# CompletePCB.net
KiCad netlist of a schematic drawn in EAGLE
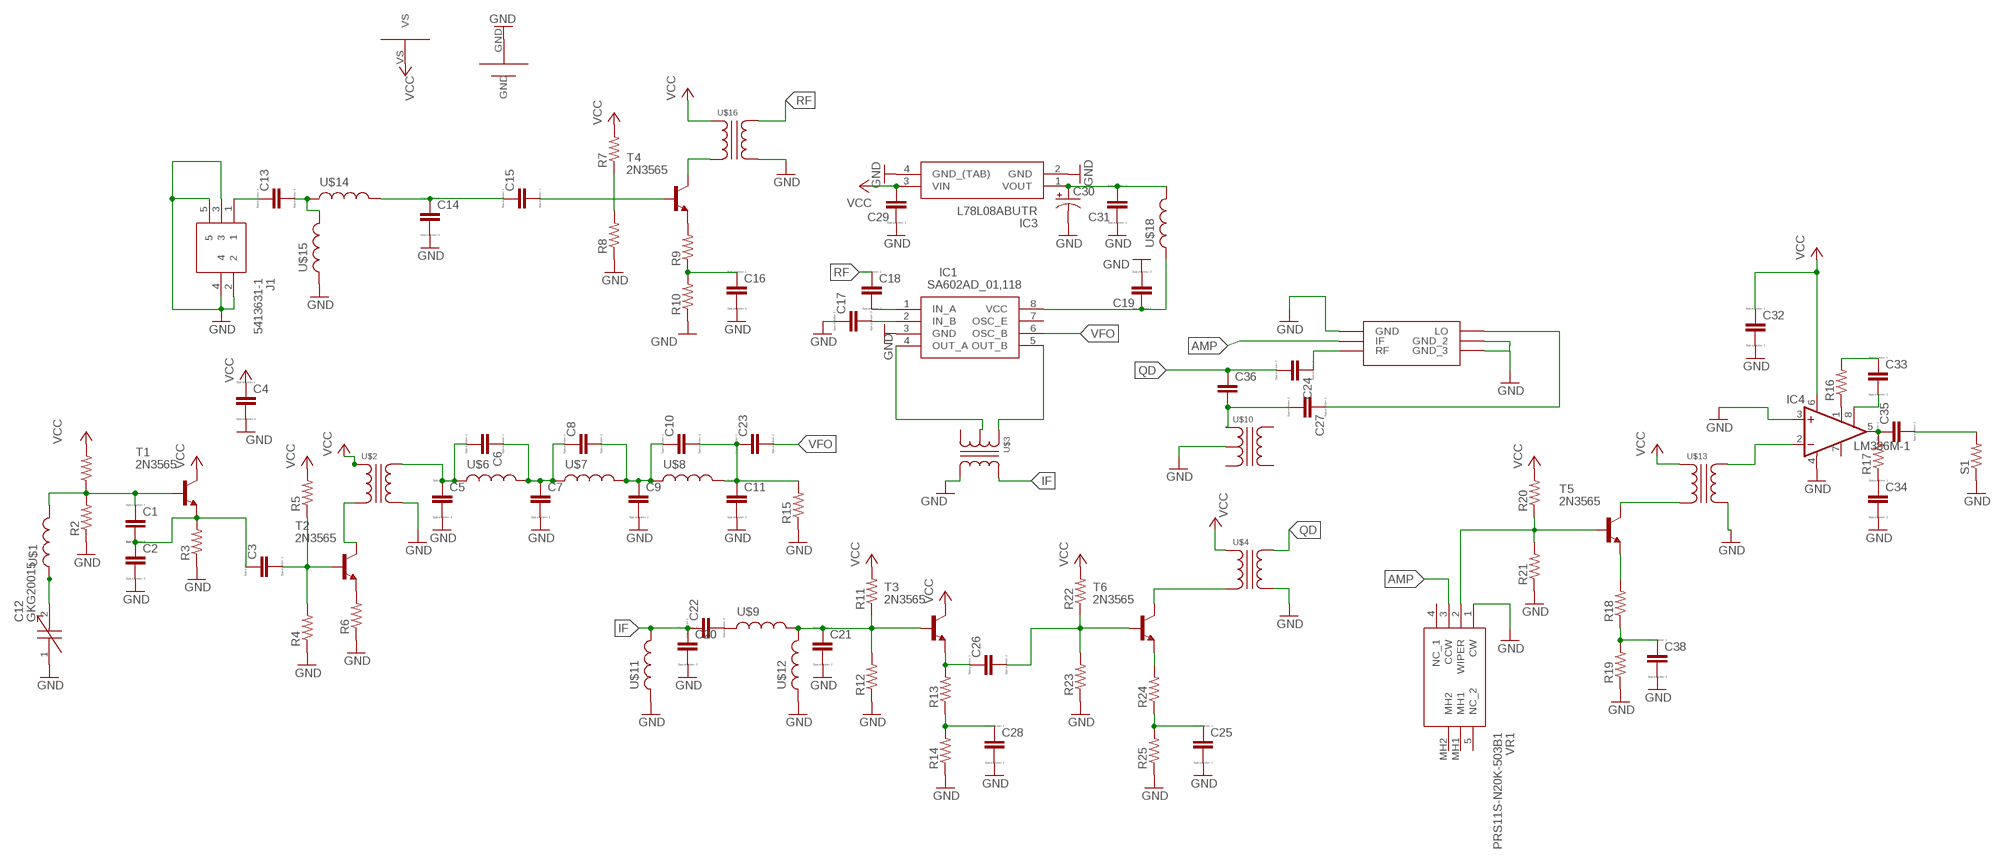
[diagram p0: schematic, sheet 1]

(export (version "E")
  (design (tool "Eeschema 10.0.6"))
  (components
    (comp (ref "C1") (value "C") (footprint "eagle-import:C0805") (libsource (lib "eagle-import") (part "C")))
    (comp (ref "C2") (value "C") (footprint "eagle-import:C0805") (libsource (lib "eagle-import") (part "C")))
    (comp (ref "C3") (value "C") (footprint "eagle-import:C0805") (libsource (lib "eagle-import") (part "C")))
    (comp (ref "C4") (value "C") (footprint "eagle-import:C0805") (libsource (lib "eagle-import") (part "C")))
    (comp (ref "C5") (value "C") (footprint "eagle-import:C0805") (libsource (lib "eagle-import") (part "C")))
    (comp (ref "C6") (value "C") (footprint "eagle-import:C0805") (libsource (lib "eagle-import") (part "C")))
    (comp (ref "C7") (value "C") (footprint "eagle-import:C0805") (libsource (lib "eagle-import") (part "C")))
    (comp (ref "C8") (value "C") (footprint "eagle-import:C0805") (libsource (lib "eagle-import") (part "C")))
    (comp (ref "C9") (value "C") (footprint "eagle-import:C0805") (libsource (lib "eagle-import") (part "C")))
    (comp (ref "C10")
      (value "C")
      (footprint "eagle-import:C0805")
      (libsource (lib "eagle-import") (part "C"))
    )
    (comp (ref "C11")
      (value "C")
      (footprint "eagle-import:C0805")
      (libsource (lib "eagle-import") (part "C"))
    )
    (comp (ref "C12")
      (value "GKG20015")
      (footprint "eagle-import:GKG20015")
      (fields (field (name "MOUSER_PART_NUMBER") "659-GKG20015"))
      (libsource (lib "eagle-import") (part "GKG20015"))
    )
    (comp (ref "C13")
      (value "C")
      (footprint "eagle-import:C0805")
      (libsource (lib "eagle-import") (part "C"))
    )
    (comp (ref "C14")
      (value "C")
      (footprint "eagle-import:C0805")
      (libsource (lib "eagle-import") (part "C"))
    )
    (comp (ref "C15")
      (value "C")
      (footprint "eagle-import:C0805")
      (libsource (lib "eagle-import") (part "C"))
    )
    (comp (ref "C16")
      (value "C")
      (footprint "eagle-import:C0805")
      (libsource (lib "eagle-import") (part "C"))
    )
    (comp (ref "C17")
      (value "C")
      (footprint "eagle-import:C0805")
      (libsource (lib "eagle-import") (part "C"))
    )
    (comp (ref "C18")
      (value "C")
      (footprint "eagle-import:C0805")
      (libsource (lib "eagle-import") (part "C"))
    )
    (comp (ref "C19")
      (value "C")
      (footprint "eagle-import:C0805")
      (libsource (lib "eagle-import") (part "C"))
    )
    (comp (ref "C20")
      (value "C")
      (footprint "eagle-import:C0805")
      (libsource (lib "eagle-import") (part "C"))
    )
    (comp (ref "C21")
      (value "C")
      (footprint "eagle-import:C0805")
      (libsource (lib "eagle-import") (part "C"))
    )
    (comp (ref "C22")
      (value "C")
      (footprint "eagle-import:C0805")
      (libsource (lib "eagle-import") (part "C"))
    )
    (comp (ref "C23")
      (value "C")
      (footprint "eagle-import:C0805")
      (libsource (lib "eagle-import") (part "C"))
    )
    (comp (ref "C24")
      (value "C")
      (footprint "eagle-import:C0805")
      (libsource (lib "eagle-import") (part "C"))
    )
    (comp (ref "C25")
      (value "C")
      (footprint "eagle-import:C0805")
      (libsource (lib "eagle-import") (part "C"))
    )
    (comp (ref "C26")
      (value "C")
      (footprint "eagle-import:C0805")
      (libsource (lib "eagle-import") (part "C"))
    )
    (comp (ref "C27")
      (value "C")
      (footprint "eagle-import:C0805")
      (libsource (lib "eagle-import") (part "C"))
    )
    (comp (ref "C28")
      (value "C")
      (footprint "eagle-import:C0805")
      (libsource (lib "eagle-import") (part "C"))
    )
    (comp (ref "C29")
      (value "C")
      (footprint "eagle-import:C0805")
      (libsource (lib "eagle-import") (part "C"))
    )
    (comp (ref "C30")
      (value "CPOL-US175TMP-0808")
      (footprint "eagle-import:175TMP-0808")
      (libsource (lib "eagle-import") (part "CPOL-US175TMP-0808"))
    )
    (comp (ref "C31")
      (value "C")
      (footprint "eagle-import:C0805")
      (libsource (lib "eagle-import") (part "C"))
    )
    (comp (ref "C32")
      (value "C")
      (footprint "eagle-import:C0805")
      (libsource (lib "eagle-import") (part "C"))
    )
    (comp (ref "C33")
      (value "C")
      (footprint "eagle-import:C0805")
      (libsource (lib "eagle-import") (part "C"))
    )
    (comp (ref "C34")
      (value "C")
      (footprint "eagle-import:C0805")
      (libsource (lib "eagle-import") (part "C"))
    )
    (comp (ref "C35")
      (value "C")
      (footprint "eagle-import:C0805")
      (libsource (lib "eagle-import") (part "C"))
    )
    (comp (ref "C36")
      (value "C-EUC0603")
      (footprint "eagle-import:C0603")
      (libsource (lib "eagle-import") (part "C-EUC0603"))
    )
    (comp (ref "C38")
      (value "C")
      (footprint "eagle-import:C0805")
      (libsource (lib "eagle-import") (part "C"))
    )
    (comp (ref "IC1")
      (value "SA602AD_01,118")
      (footprint "eagle-import:SOIC127P600X175-8N")
      (fields
        (field (name "MANUFACTURER_PART_NUMBER") "SA602AD/01,118")
        (field (name "MOUSER_PART_NUMBER") "771-SA602AD/01-T")
      )
      (libsource (lib "eagle-import") (part "SA602AD_01,118"))
    )
    (comp (ref "IC3")
      (value "L78L08ABUTR")
      (footprint "eagle-import:ST-SOT-89")
      (fields (field (name "MOUSER_PART_NUMBER") "511-L78L08ABU"))
      (libsource (lib "eagle-import") (part "L78L08ABUTR"))
    )
    (comp (ref "IC4")
      (value "LM386M-1")
      (footprint "eagle-import:SO08")
      (libsource (lib "eagle-import") (part "LM386?-M1"))
    )
    (comp (ref "J1")
      (value "5413631-1")
      (footprint "eagle-import:54136311")
      (fields (field (name "MOUSER_PART_NUMBER") "571-5413631-1"))
      (libsource (lib "eagle-import") (part "5413631-1"))
    )
    (comp (ref "R1")
      (value "R-US_R0805")
      (footprint "eagle-import:R0805")
      (libsource (lib "eagle-import") (part "resistor_348_R-US_R0805"))
    )
    (comp (ref "R2")
      (value "R-US_R0805")
      (footprint "eagle-import:R0805")
      (libsource (lib "eagle-import") (part "resistor_348_R-US_R0805"))
    )
    (comp (ref "R3")
      (value "R-US_R0805")
      (footprint "eagle-import:R0805")
      (libsource (lib "eagle-import") (part "resistor_348_R-US_R0805"))
    )
    (comp (ref "R4")
      (value "R-US_R0805")
      (footprint "eagle-import:R0805")
      (libsource (lib "eagle-import") (part "resistor_348_R-US_R0805"))
    )
    (comp (ref "R5")
      (value "R-US_R0805")
      (footprint "eagle-import:R0805")
      (libsource (lib "eagle-import") (part "resistor_348_R-US_R0805"))
    )
    (comp (ref "R6")
      (value "R-US_R0805")
      (footprint "eagle-import:R0805")
      (libsource (lib "eagle-import") (part "resistor_348_R-US_R0805"))
    )
    (comp (ref "R7")
      (value "R-US_R0805")
      (footprint "eagle-import:R0805")
      (libsource (lib "eagle-import") (part "resistor_348_R-US_R0805"))
    )
    (comp (ref "R8")
      (value "R-US_R0805")
      (footprint "eagle-import:R0805")
      (libsource (lib "eagle-import") (part "resistor_348_R-US_R0805"))
    )
    (comp (ref "R9")
      (value "R-US_R0805")
      (footprint "eagle-import:R0805")
      (libsource (lib "eagle-import") (part "resistor_348_R-US_R0805"))
    )
    (comp (ref "R10")
      (value "R-US_R0805")
      (footprint "eagle-import:R0805")
      (libsource (lib "eagle-import") (part "resistor_348_R-US_R0805"))
    )
    (comp (ref "R11")
      (value "R-US_R0805")
      (footprint "eagle-import:R0805")
      (libsource (lib "eagle-import") (part "resistor_348_R-US_R0805"))
    )
    (comp (ref "R12")
      (value "R-US_R0805")
      (footprint "eagle-import:R0805")
      (libsource (lib "eagle-import") (part "resistor_348_R-US_R0805"))
    )
    (comp (ref "R13")
      (value "R-US_R0805")
      (footprint "eagle-import:R0805")
      (libsource (lib "eagle-import") (part "resistor_348_R-US_R0805"))
    )
    (comp (ref "R14")
      (value "R-US_R0805")
      (footprint "eagle-import:R0805")
      (libsource (lib "eagle-import") (part "resistor_348_R-US_R0805"))
    )
    (comp (ref "R15")
      (value "R-US_R0805")
      (footprint "eagle-import:R0805")
      (libsource (lib "eagle-import") (part "resistor_348_R-US_R0805"))
    )
    (comp (ref "R16")
      (value "R-US_R0805")
      (footprint "eagle-import:R0805")
      (libsource (lib "eagle-import") (part "resistor_348_R-US_R0805"))
    )
    (comp (ref "R17")
      (value "R-US_R0805")
      (footprint "eagle-import:R0805")
      (libsource (lib "eagle-import") (part "resistor_348_R-US_R0805"))
    )
    (comp (ref "R18")
      (value "R-US_R0805")
      (footprint "eagle-import:R0805")
      (libsource (lib "eagle-import") (part "resistor_348_R-US_R0805"))
    )
    (comp (ref "R19")
      (value "R-US_R0805")
      (footprint "eagle-import:R0805")
      (libsource (lib "eagle-import") (part "resistor_348_R-US_R0805"))
    )
    (comp (ref "R20")
      (value "R-US_R0805")
      (footprint "eagle-import:R0805")
      (libsource (lib "eagle-import") (part "resistor_348_R-US_R0805"))
    )
    (comp (ref "R21")
      (value "R-US_R0805")
      (footprint "eagle-import:R0805")
      (libsource (lib "eagle-import") (part "resistor_348_R-US_R0805"))
    )
    (comp (ref "R22")
      (value "R-US_R0805")
      (footprint "eagle-import:R0805")
      (libsource (lib "eagle-import") (part "resistor_348_R-US_R0805"))
    )
    (comp (ref "R23")
      (value "R-US_R0805")
      (footprint "eagle-import:R0805")
      (libsource (lib "eagle-import") (part "resistor_348_R-US_R0805"))
    )
    (comp (ref "R24")
      (value "R-US_R0805")
      (footprint "eagle-import:R0805")
      (libsource (lib "eagle-import") (part "resistor_348_R-US_R0805"))
    )
    (comp (ref "R25")
      (value "R-US_R0805")
      (footprint "eagle-import:R0805")
      (libsource (lib "eagle-import") (part "resistor_348_R-US_R0805"))
    )
    (comp (ref "S1")
      (value "R-US_0207/5V")
      (footprint "eagle-import:0207_5V")
      (libsource (lib "eagle-import") (part "R-US_0207/5V"))
    )
    (comp (ref "T1")
      (value "2N3565")
      (footprint "eagle-import:TO92")
      (libsource (lib "eagle-import") (part "2N3565"))
    )
    (comp (ref "T2")
      (value "2N3565")
      (footprint "eagle-import:TO92")
      (libsource (lib "eagle-import") (part "2N3565"))
    )
    (comp (ref "T3")
      (value "2N3565")
      (footprint "eagle-import:TO92")
      (libsource (lib "eagle-import") (part "2N3565"))
    )
    (comp (ref "T4")
      (value "2N3565")
      (footprint "eagle-import:TO92")
      (libsource (lib "eagle-import") (part "2N3565"))
    )
    (comp (ref "T5")
      (value "2N3565")
      (footprint "eagle-import:TO92")
      (libsource (lib "eagle-import") (part "2N3565"))
    )
    (comp (ref "T6")
      (value "2N3565")
      (footprint "eagle-import:TO92")
      (libsource (lib "eagle-import") (part "2N3565"))
    )
    (comp (ref "U$1")
      (value "WOUNDINDUCTOR")
      (footprint "eagle-import:WOUNDINDUCTOR")
      (libsource (lib "eagle-import") (part "WOUNDINDUCTOR"))
    )
    (comp (ref "U$2")
      (value "RFTRANSFORMER")
      (footprint "eagle-import:RFTRABSFORMER")
      (libsource (lib "eagle-import") (part "RFTRANSFORMER"))
    )
    (comp (ref "U$3")
      (value "42IF123")
      (footprint "eagle-import:42IF123")
      (libsource (lib "eagle-import") (part "42IF123"))
    )
    (comp (ref "U$4")
      (value "RFTRANSFORMER")
      (footprint "eagle-import:RFTRABSFORMER")
      (libsource (lib "eagle-import") (part "RFTRANSFORMER"))
    )
    (comp (ref "U$5")
      (value "ALLIGATORCLIPS")
      (footprint "eagle-import:ALLIGATORCONNECTOR")
      (libsource (lib "eagle-import") (part "ALLIGATORCLIPS"))
    )
    (comp (ref "U$6")
      (value "WOUNDINDUCTOR")
      (footprint "eagle-import:WOUNDINDUCTOR")
      (libsource (lib "eagle-import") (part "WOUNDINDUCTOR"))
    )
    (comp (ref "U$7")
      (value "WOUNDINDUCTOR")
      (footprint "eagle-import:WOUNDINDUCTOR")
      (libsource (lib "eagle-import") (part "WOUNDINDUCTOR"))
    )
    (comp (ref "U$8")
      (value "WOUNDINDUCTOR")
      (footprint "eagle-import:WOUNDINDUCTOR")
      (libsource (lib "eagle-import") (part "WOUNDINDUCTOR"))
    )
    (comp (ref "U$9")
      (value "WOUNDINDUCTOR")
      (footprint "eagle-import:WOUNDINDUCTOR")
      (libsource (lib "eagle-import") (part "WOUNDINDUCTOR"))
    )
    (comp (ref "U$10")
      (value "42IF123")
      (footprint "eagle-import:42IF123")
      (libsource (lib "eagle-import") (part "42IF123"))
    )
    (comp (ref "U$11")
      (value "WOUNDINDUCTOR")
      (footprint "eagle-import:WOUNDINDUCTOR")
      (libsource (lib "eagle-import") (part "WOUNDINDUCTOR"))
    )
    (comp (ref "U$12")
      (value "WOUNDINDUCTOR")
      (footprint "eagle-import:WOUNDINDUCTOR")
      (libsource (lib "eagle-import") (part "WOUNDINDUCTOR"))
    )
    (comp (ref "U$13")
      (value "RFTRANSFORMER")
      (footprint "eagle-import:RFTRABSFORMER")
      (libsource (lib "eagle-import") (part "RFTRANSFORMER"))
    )
    (comp (ref "U$14")
      (value "WOUNDINDUCTOR")
      (footprint "eagle-import:WOUNDINDUCTOR")
      (libsource (lib "eagle-import") (part "WOUNDINDUCTOR"))
    )
    (comp (ref "U$15")
      (value "WOUNDINDUCTOR")
      (footprint "eagle-import:WOUNDINDUCTOR")
      (libsource (lib "eagle-import") (part "WOUNDINDUCTOR"))
    )
    (comp (ref "U$16")
      (value "RFTRANSFORMER")
      (footprint "eagle-import:RFTRABSFORMER")
      (libsource (lib "eagle-import") (part "RFTRANSFORMER"))
    )
    (comp (ref "U$17")
      (value "ADE-1")
      (footprint "eagle-import:ADE-1")
      (libsource (lib "eagle-import") (part "ADE-1"))
    )
    (comp (ref "U$18")
      (value "WOUNDINDUCTOR")
      (footprint "eagle-import:WOUNDINDUCTOR")
      (libsource (lib "eagle-import") (part "WOUNDINDUCTOR"))
    )
    (comp (ref "VR1")
      (value "PRS11S-N20K-503B1")
      (footprint "eagle-import:PRS11SN20K503B1")
      (fields (field (name "MOUSER_PART_NUMBER") "652-PRS11SN20K503B1"))
      (libsource (lib "eagle-import") (part "PRS11S-N20K-503B1"))
    )
  )
  (nets
    (net (code "1") (name "AMP") (class "Default")
      (node (ref "U$17") (pin "IF") (pinfunction "IF_IF") (pintype "bidirectional"))
      (node (ref "VR1") (pin "3") (pinfunction "CCW_3") (pintype "bidirectional"))
    )
    (net (code "2") (name "GND") (class "Default")
      (node (ref "C11") (pin "2") (pinfunction "2_2") (pintype "passive"))
      (node (ref "C12") (pin "1") (pinfunction "1_1") (pintype "bidirectional"))
      (node (ref "C14") (pin "2") (pinfunction "2_2") (pintype "passive"))
      (node (ref "C16") (pin "2") (pinfunction "2_2") (pintype "passive"))
      (node (ref "C17") (pin "1") (pinfunction "1_1") (pintype "passive"))
      (node (ref "C19") (pin "2") (pinfunction "2_2") (pintype "passive"))
      (node (ref "C2") (pin "2") (pinfunction "2_2") (pintype "passive"))
      (node (ref "C20") (pin "2") (pinfunction "2_2") (pintype "passive"))
      (node (ref "C21") (pin "2") (pinfunction "2_2") (pintype "passive"))
      (node (ref "C25") (pin "2") (pinfunction "2_2") (pintype "passive"))
      (node (ref "C28") (pin "2") (pinfunction "2_2") (pintype "passive"))
      (node (ref "C29") (pin "1") (pinfunction "1_1") (pintype "passive"))
      (node (ref "C30") (pin "-") (pinfunction "-_-") (pintype "passive"))
      (node (ref "C31") (pin "1") (pinfunction "1_1") (pintype "passive"))
      (node (ref "C32") (pin "2") (pinfunction "2_2") (pintype "passive"))
      (node (ref "C34") (pin "2") (pinfunction "2_2") (pintype "passive"))
      (node (ref "C38") (pin "2") (pinfunction "2_2") (pintype "passive"))
      (node (ref "C4") (pin "2") (pinfunction "2_2") (pintype "passive"))
      (node (ref "C5") (pin "2") (pinfunction "2_2") (pintype "passive"))
      (node (ref "C7") (pin "2") (pinfunction "2_2") (pintype "passive"))
      (node (ref "C9") (pin "2") (pinfunction "2_2") (pintype "passive"))
      (node (ref "IC1") (pin "3") (pinfunction "GND_3") (pintype "power_in"))
      (node (ref "IC3") (pin "2") (pinfunction "GND_2") (pintype "power_in"))
      (node (ref "IC3") (pin "4") (pinfunction "GND_(TAB)_4") (pintype "power_in"))
      (node (ref "IC4") (pin "3") (pinfunction "+IN_3") (pintype "input"))
      (node (ref "IC4") (pin "4") (pinfunction "GND_4") (pintype "power_in"))
      (node (ref "J1") (pin "2") (pinfunction "2_2") (pintype "bidirectional"))
      (node (ref "J1") (pin "3") (pinfunction "3_3") (pintype "bidirectional"))
      (node (ref "J1") (pin "4") (pinfunction "4_4") (pintype "bidirectional"))
      (node (ref "J1") (pin "5") (pinfunction "5_5") (pintype "bidirectional"))
      (node (ref "R10") (pin "1") (pinfunction "1_1") (pintype "passive"))
      (node (ref "R12") (pin "1") (pinfunction "1_1") (pintype "passive"))
      (node (ref "R14") (pin "1") (pinfunction "1_1") (pintype "passive"))
      (node (ref "R15") (pin "1") (pinfunction "1_1") (pintype "passive"))
      (node (ref "R19") (pin "1") (pinfunction "1_1") (pintype "passive"))
      (node (ref "R2") (pin "1") (pinfunction "1_1") (pintype "passive"))
      (node (ref "R21") (pin "1") (pinfunction "1_1") (pintype "passive"))
      (node (ref "R23") (pin "1") (pinfunction "1_1") (pintype "passive"))
      (node (ref "R25") (pin "1") (pinfunction "1_1") (pintype "passive"))
      (node (ref "R3") (pin "1") (pinfunction "1_1") (pintype "passive"))
      (node (ref "R4") (pin "1") (pinfunction "1_1") (pintype "passive"))
      (node (ref "R6") (pin "1") (pinfunction "1_1") (pintype "passive"))
      (node (ref "R8") (pin "1") (pinfunction "1_1") (pintype "passive"))
      (node (ref "S1") (pin "1") (pinfunction "1_1") (pintype "passive"))
      (node (ref "U$10") (pin "P$1") (pinfunction "P$5_P$1") (pintype "bidirectional"))
      (node (ref "U$11") (pin "1") (pinfunction "1_1") (pintype "bidirectional"))
      (node (ref "U$12") (pin "1") (pinfunction "1_1") (pintype "bidirectional"))
      (node (ref "U$13") (pin "P$4") (pinfunction "P$3_P$4") (pintype "bidirectional"))
      (node (ref "U$15") (pin "1") (pinfunction "1_1") (pintype "bidirectional"))
      (node (ref "U$16") (pin "P$4") (pinfunction "P$3_P$4") (pintype "bidirectional"))
      (node (ref "U$17") (pin "GND") (pinfunction "GND_GND") (pintype "bidirectional"))
      (node (ref "U$17") (pin "GND2") (pinfunction "GND_2_GND2") (pintype "bidirectional"))
      (node (ref "U$17") (pin "GND3") (pinfunction "GND_3_GND3") (pintype "bidirectional"))
      (node (ref "U$2") (pin "P$4") (pinfunction "P$3_P$4") (pintype "bidirectional"))
      (node (ref "U$3") (pin "P$4") (pinfunction "P$3_P$4") (pintype "bidirectional"))
      (node (ref "U$4") (pin "P$4") (pinfunction "P$3_P$4") (pintype "bidirectional"))
      (node (ref "U$5") (pin "GND") (pinfunction "GND_GND") (pintype "bidirectional"))
      (node (ref "VR1") (pin "1") (pinfunction "CW_1") (pintype "bidirectional"))
    )
    (net (code "3") (name "IF") (class "Default")
      (node (ref "C20") (pin "1") (pinfunction "1_1") (pintype "passive"))
      (node (ref "C22") (pin "1") (pinfunction "1_1") (pintype "passive"))
      (node (ref "U$11") (pin "2") (pinfunction "2_2") (pintype "bidirectional"))
      (node (ref "U$3") (pin "P$5") (pinfunction "P$4_P$5") (pintype "bidirectional"))
    )
    (net (code "4") (name "Net-(C6-Pad1)") (class "Default")
      (node (ref "C6") (pin "1") (pinfunction "1_1") (pintype "passive"))
      (node (ref "C7") (pin "1") (pinfunction "1_1") (pintype "passive"))
      (node (ref "C8") (pin "1") (pinfunction "1_1") (pintype "passive"))
      (node (ref "U$6") (pin "2") (pinfunction "2_2") (pintype "bidirectional"))
      (node (ref "U$7") (pin "1") (pinfunction "1_1") (pintype "bidirectional"))
    )
    (net (code "5") (name "Net-(C10-Pad1)") (class "Default")
      (node (ref "C10") (pin "1") (pinfunction "1_1") (pintype "passive"))
      (node (ref "C8") (pin "2") (pinfunction "2_2") (pintype "passive"))
      (node (ref "C9") (pin "1") (pinfunction "1_1") (pintype "passive"))
      (node (ref "U$7") (pin "2") (pinfunction "2_2") (pintype "bidirectional"))
      (node (ref "U$8") (pin "1") (pinfunction "1_1") (pintype "bidirectional"))
    )
    (net (code "6") (name "Net-(C10-Pad2)") (class "Default")
      (node (ref "C10") (pin "2") (pinfunction "2_2") (pintype "passive"))
      (node (ref "C11") (pin "1") (pinfunction "1_1") (pintype "passive"))
      (node (ref "C23") (pin "1") (pinfunction "1_1") (pintype "passive"))
      (node (ref "R15") (pin "2") (pinfunction "2_2") (pintype "passive"))
      (node (ref "U$8") (pin "2") (pinfunction "2_2") (pintype "bidirectional"))
    )
    (net (code "7") (name "Net-(C12-Pad2)") (class "Default")
      (node (ref "C12") (pin "2") (pinfunction "2_2") (pintype "bidirectional"))
      (node (ref "U$1") (pin "1") (pinfunction "1_1") (pintype "bidirectional"))
    )
    (net (code "8") (name "Net-(C13-Pad1)") (class "Default")
      (node (ref "C13") (pin "1") (pinfunction "1_1") (pintype "passive"))
      (node (ref "J1") (pin "1") (pinfunction "1_1") (pintype "bidirectional"))
    )
    (net (code "9") (name "Net-(C13-Pad2)") (class "Default")
      (node (ref "C13") (pin "2") (pinfunction "2_2") (pintype "passive"))
      (node (ref "U$14") (pin "1") (pinfunction "1_1") (pintype "bidirectional"))
      (node (ref "U$15") (pin "2") (pinfunction "2_2") (pintype "bidirectional"))
    )
    (net (code "10") (name "Net-(C14-Pad1)") (class "Default")
      (node (ref "C14") (pin "1") (pinfunction "1_1") (pintype "passive"))
      (node (ref "C15") (pin "1") (pinfunction "1_1") (pintype "passive"))
      (node (ref "U$14") (pin "2") (pinfunction "2_2") (pintype "bidirectional"))
    )
    (net (code "11") (name "Net-(C16-Pad1)") (class "Default")
      (node (ref "C16") (pin "1") (pinfunction "1_1") (pintype "passive"))
      (node (ref "R10") (pin "2") (pinfunction "2_2") (pintype "passive"))
      (node (ref "R9") (pin "1") (pinfunction "1_1") (pintype "passive"))
    )
    (net (code "12") (name "Net-(C22-Pad2)") (class "Default")
      (node (ref "C22") (pin "2") (pinfunction "2_2") (pintype "passive"))
      (node (ref "U$9") (pin "1") (pinfunction "1_1") (pintype "bidirectional"))
    )
    (net (code "13") (name "Net-(C24-Pad1)") (class "Default")
      (node (ref "C24") (pin "1") (pinfunction "1_1") (pintype "passive"))
      (node (ref "U$17") (pin "RF") (pinfunction "RF_RF") (pintype "bidirectional"))
    )
    (net (code "14") (name "Net-(C25-Pad1)") (class "Default")
      (node (ref "C25") (pin "1") (pinfunction "1_1") (pintype "passive"))
      (node (ref "R24") (pin "1") (pinfunction "1_1") (pintype "passive"))
      (node (ref "R25") (pin "2") (pinfunction "2_2") (pintype "passive"))
    )
    (net (code "15") (name "Net-(C27-Pad1)") (class "Default")
      (node (ref "C27") (pin "1") (pinfunction "1_1") (pintype "passive"))
      (node (ref "U$17") (pin "LO") (pinfunction "LO_LO") (pintype "bidirectional"))
    )
    (net (code "16") (name "Net-(C28-Pad1)") (class "Default")
      (node (ref "C28") (pin "1") (pinfunction "1_1") (pintype "passive"))
      (node (ref "R13") (pin "1") (pinfunction "1_1") (pintype "passive"))
      (node (ref "R14") (pin "2") (pinfunction "2_2") (pintype "passive"))
    )
    (net (code "17") (name "Net-(C33-Pad1)") (class "Default")
      (node (ref "C33") (pin "1") (pinfunction "1_1") (pintype "passive"))
      (node (ref "R16") (pin "2") (pinfunction "2_2") (pintype "passive"))
    )
    (net (code "18") (name "Net-(C33-Pad2)") (class "Default")
      (node (ref "C33") (pin "2") (pinfunction "2_2") (pintype "passive"))
      (node (ref "IC4") (pin "8") (pinfunction "GAIN_8") (pintype "passive"))
    )
    (net (code "19") (name "Net-(C34-Pad1)") (class "Default")
      (node (ref "C34") (pin "1") (pinfunction "1_1") (pintype "passive"))
      (node (ref "R17") (pin "1") (pinfunction "1_1") (pintype "passive"))
    )
    (net (code "20") (name "Net-(C35-Pad2)") (class "Default")
      (node (ref "C35") (pin "2") (pinfunction "2_2") (pintype "passive"))
      (node (ref "S1") (pin "2") (pinfunction "2_2") (pintype "passive"))
    )
    (net (code "21") (name "Net-(C38-Pad1)") (class "Default")
      (node (ref "C38") (pin "1") (pinfunction "1_1") (pintype "passive"))
      (node (ref "R18") (pin "1") (pinfunction "1_1") (pintype "passive"))
      (node (ref "R19") (pin "2") (pinfunction "2_2") (pintype "passive"))
    )
    (net (code "22") (name "Net-(IC1-IN_A)") (class "Default")
      (node (ref "C18") (pin "2") (pinfunction "2_2") (pintype "passive"))
      (node (ref "IC1") (pin "1") (pinfunction "IN_A_1") (pintype "input"))
    )
    (net (code "23") (name "Net-(IC1-IN_B)") (class "Default")
      (node (ref "C17") (pin "2") (pinfunction "2_2") (pintype "passive"))
      (node (ref "IC1") (pin "2") (pinfunction "IN_B_2") (pintype "input"))
    )
    (net (code "24") (name "Net-(IC1-OUT_A)") (class "Default")
      (node (ref "IC1") (pin "4") (pinfunction "OUT_A_4") (pintype "output"))
      (node (ref "U$3") (pin "P$1") (pinfunction "P$5_P$1") (pintype "bidirectional"))
    )
    (net (code "25") (name "Net-(IC1-OUT_B)") (class "Default")
      (node (ref "IC1") (pin "5") (pinfunction "OUT_B_5") (pintype "output"))
      (node (ref "U$3") (pin "P$2") (pinfunction "P$1_P$2") (pintype "bidirectional"))
    )
    (net (code "26") (name "Net-(IC1-VCC)") (class "Default")
      (node (ref "C19") (pin "1") (pinfunction "1_1") (pintype "passive"))
      (node (ref "IC1") (pin "8") (pinfunction "VCC_8") (pintype "power_in"))
      (node (ref "U$18") (pin "1") (pinfunction "1_1") (pintype "bidirectional"))
    )
    (net (code "27") (name "Net-(IC3-VOUT)") (class "Default")
      (node (ref "C30") (pin "+") (pinfunction "+_+") (pintype "passive"))
      (node (ref "C31") (pin "2") (pinfunction "2_2") (pintype "passive"))
      (node (ref "IC3") (pin "1") (pinfunction "VOUT_1") (pintype "output"))
      (node (ref "U$18") (pin "2") (pinfunction "2_2") (pintype "bidirectional"))
    )
    (net (code "28") (name "Net-(IC4--IN)") (class "Default")
      (node (ref "IC4") (pin "2") (pinfunction "-IN_2") (pintype "input"))
      (node (ref "U$13") (pin "P$3") (pinfunction "P$4_P$3") (pintype "bidirectional"))
    )
    (net (code "29") (name "Net-(IC4-GAIN-Pad1)") (class "Default")
      (node (ref "IC4") (pin "1") (pinfunction "GAIN_1") (pintype "passive"))
      (node (ref "R16") (pin "1") (pinfunction "1_1") (pintype "passive"))
    )
    (net (code "30") (name "Net-(IC4-OUT)") (class "Default")
      (node (ref "C35") (pin "1") (pinfunction "1_1") (pintype "passive"))
      (node (ref "IC4") (pin "5") (pinfunction "OUT_5") (pintype "output"))
      (node (ref "R17") (pin "2") (pinfunction "2_2") (pintype "passive"))
    )
    (net (code "31") (name "Net-(R7-Pad1)") (class "Default")
      (node (ref "R7") (pin "1") (pinfunction "1_1") (pintype "passive"))
      (node (ref "R8") (pin "2") (pinfunction "2_2") (pintype "passive"))
    )
    (net (code "32") (name "Net-(T1-B)") (class "Default")
      (node (ref "C1") (pin "1") (pinfunction "1_1") (pintype "passive"))
      (node (ref "R1") (pin "1") (pinfunction "1_1") (pintype "passive"))
      (node (ref "R2") (pin "2") (pinfunction "2_2") (pintype "passive"))
      (node (ref "T1") (pin "2") (pinfunction "B_2") (pintype "passive"))
      (node (ref "U$1") (pin "2") (pinfunction "2_2") (pintype "bidirectional"))
    )
    (net (code "33") (name "Net-(T1-E)") (class "Default")
      (node (ref "C1") (pin "2") (pinfunction "2_2") (pintype "passive"))
      (node (ref "C2") (pin "1") (pinfunction "1_1") (pintype "passive"))
      (node (ref "C3") (pin "1") (pinfunction "1_1") (pintype "passive"))
      (node (ref "R3") (pin "2") (pinfunction "2_2") (pintype "passive"))
      (node (ref "T1") (pin "3") (pinfunction "E_3") (pintype "passive"))
    )
    (net (code "34") (name "Net-(T2-B)") (class "Default")
      (node (ref "C3") (pin "2") (pinfunction "2_2") (pintype "passive"))
      (node (ref "R4") (pin "2") (pinfunction "2_2") (pintype "passive"))
      (node (ref "R5") (pin "1") (pinfunction "1_1") (pintype "passive"))
      (node (ref "T2") (pin "2") (pinfunction "B_2") (pintype "passive"))
    )
    (net (code "35") (name "Net-(T2-C)") (class "Default")
      (node (ref "T2") (pin "1") (pinfunction "C_1") (pintype "passive"))
      (node (ref "U$2") (pin "P$2") (pinfunction "P$2_P$2") (pintype "bidirectional"))
    )
    (net (code "36") (name "Net-(T2-E)") (class "Default")
      (node (ref "R6") (pin "2") (pinfunction "2_2") (pintype "passive"))
      (node (ref "T2") (pin "3") (pinfunction "E_3") (pintype "passive"))
    )
    (net (code "37") (name "Net-(T3-B)") (class "Default")
      (node (ref "C21") (pin "1") (pinfunction "1_1") (pintype "passive"))
      (node (ref "R11") (pin "1") (pinfunction "1_1") (pintype "passive"))
      (node (ref "R12") (pin "2") (pinfunction "2_2") (pintype "passive"))
      (node (ref "T3") (pin "2") (pinfunction "B_2") (pintype "passive"))
      (node (ref "U$12") (pin "2") (pinfunction "2_2") (pintype "bidirectional"))
      (node (ref "U$9") (pin "2") (pinfunction "2_2") (pintype "bidirectional"))
    )
    (net (code "38") (name "Net-(T3-E)") (class "Default")
      (node (ref "C26") (pin "1") (pinfunction "1_1") (pintype "passive"))
      (node (ref "R13") (pin "2") (pinfunction "2_2") (pintype "passive"))
      (node (ref "T3") (pin "3") (pinfunction "E_3") (pintype "passive"))
    )
    (net (code "39") (name "Net-(T4-B)") (class "Default")
      (node (ref "C15") (pin "2") (pinfunction "2_2") (pintype "passive"))
      (node (ref "T4") (pin "2") (pinfunction "B_2") (pintype "passive"))
    )
    (net (code "40") (name "Net-(T4-C)") (class "Default")
      (node (ref "T4") (pin "1") (pinfunction "C_1") (pintype "passive"))
      (node (ref "U$16") (pin "P$2") (pinfunction "P$2_P$2") (pintype "bidirectional"))
    )
    (net (code "41") (name "Net-(T4-E)") (class "Default")
      (node (ref "R9") (pin "2") (pinfunction "2_2") (pintype "passive"))
      (node (ref "T4") (pin "3") (pinfunction "E_3") (pintype "passive"))
    )
    (net (code "42") (name "Net-(T5-B)") (class "Default")
      (node (ref "R20") (pin "1") (pinfunction "1_1") (pintype "passive"))
      (node (ref "R21") (pin "2") (pinfunction "2_2") (pintype "passive"))
      (node (ref "T5") (pin "2") (pinfunction "B_2") (pintype "passive"))
      (node (ref "VR1") (pin "2") (pinfunction "WIPER_2") (pintype "bidirectional"))
    )
    (net (code "43") (name "Net-(T5-C)") (class "Default")
      (node (ref "T5") (pin "1") (pinfunction "C_1") (pintype "passive"))
      (node (ref "U$13") (pin "P$2") (pinfunction "P$2_P$2") (pintype "bidirectional"))
    )
    (net (code "44") (name "Net-(T5-E)") (class "Default")
      (node (ref "R18") (pin "2") (pinfunction "2_2") (pintype "passive"))
      (node (ref "T5") (pin "3") (pinfunction "E_3") (pintype "passive"))
    )
    (net (code "45") (name "Net-(T6-B)") (class "Default")
      (node (ref "C26") (pin "2") (pinfunction "2_2") (pintype "passive"))
      (node (ref "R22") (pin "1") (pinfunction "1_1") (pintype "passive"))
      (node (ref "R23") (pin "2") (pinfunction "2_2") (pintype "passive"))
      (node (ref "T6") (pin "2") (pinfunction "B_2") (pintype "passive"))
    )
    (net (code "46") (name "Net-(T6-C)") (class "Default")
      (node (ref "T6") (pin "1") (pinfunction "C_1") (pintype "passive"))
      (node (ref "U$4") (pin "P$2") (pinfunction "P$2_P$2") (pintype "bidirectional"))
    )
    (net (code "47") (name "Net-(T6-E)") (class "Default")
      (node (ref "R24") (pin "2") (pinfunction "2_2") (pintype "passive"))
      (node (ref "T6") (pin "3") (pinfunction "E_3") (pintype "passive"))
    )
    (net (code "48") (name "Net-(U$2-P$4)") (class "Default")
      (node (ref "C5") (pin "1") (pinfunction "1_1") (pintype "passive"))
      (node (ref "C6") (pin "2") (pinfunction "2_2") (pintype "passive"))
      (node (ref "U$2") (pin "P$3") (pinfunction "P$4_P$3") (pintype "bidirectional"))
      (node (ref "U$6") (pin "1") (pinfunction "1_1") (pintype "bidirectional"))
    )
    (net (code "49") (name "Net-(U$10-P$1)") (class "Default")
      (node (ref "C27") (pin "2") (pinfunction "2_2") (pintype "passive"))
      (node (ref "C36") (pin "2") (pinfunction "2_2") (pintype "passive"))
      (node (ref "U$10") (pin "P$2") (pinfunction "P$1_P$2") (pintype "bidirectional"))
    )
    (net (code "50") (name "QD") (class "Default")
      (node (ref "C24") (pin "2") (pinfunction "2_2") (pintype "passive"))
      (node (ref "C36") (pin "1") (pinfunction "1_1") (pintype "passive"))
      (node (ref "U$4") (pin "P$3") (pinfunction "P$4_P$3") (pintype "bidirectional"))
    )
    (net (code "51") (name "RF") (class "Default")
      (node (ref "C18") (pin "1") (pinfunction "1_1") (pintype "passive"))
      (node (ref "U$16") (pin "P$3") (pinfunction "P$4_P$3") (pintype "bidirectional"))
    )
    (net (code "52") (name "VCC") (class "Default")
      (node (ref "C29") (pin "2") (pinfunction "2_2") (pintype "passive"))
      (node (ref "C32") (pin "1") (pinfunction "1_1") (pintype "passive"))
      (node (ref "C4") (pin "1") (pinfunction "1_1") (pintype "passive"))
      (node (ref "IC3") (pin "3") (pinfunction "VIN_3") (pintype "input"))
      (node (ref "IC4") (pin "6") (pinfunction "VS_6") (pintype "power_in"))
      (node (ref "R1") (pin "2") (pinfunction "2_2") (pintype "passive"))
      (node (ref "R11") (pin "2") (pinfunction "2_2") (pintype "passive"))
      (node (ref "R20") (pin "2") (pinfunction "2_2") (pintype "passive"))
      (node (ref "R22") (pin "2") (pinfunction "2_2") (pintype "passive"))
      (node (ref "R5") (pin "2") (pinfunction "2_2") (pintype "passive"))
      (node (ref "R7") (pin "2") (pinfunction "2_2") (pintype "passive"))
      (node (ref "T1") (pin "1") (pinfunction "C_1") (pintype "passive"))
      (node (ref "T3") (pin "1") (pinfunction "C_1") (pintype "passive"))
      (node (ref "U$13") (pin "P$1") (pinfunction "P$1_P$1") (pintype "bidirectional"))
      (node (ref "U$16") (pin "P$1") (pinfunction "P$1_P$1") (pintype "bidirectional"))
      (node (ref "U$2") (pin "P$1") (pinfunction "P$1_P$1") (pintype "bidirectional"))
      (node (ref "U$4") (pin "P$1") (pinfunction "P$1_P$1") (pintype "bidirectional"))
      (node (ref "U$5") (pin "VS") (pinfunction "VS_VS") (pintype "bidirectional"))
    )
    (net (code "53") (name "VFO") (class "Default")
      (node (ref "C23") (pin "2") (pinfunction "2_2") (pintype "passive"))
      (node (ref "IC1") (pin "6") (pinfunction "OSC_B_6") (pintype "bidirectional"))
    )
    (net (code "54") (name "unconnected-(IC1-OSC_E-Pad7)") (class "Default")
      (node (ref "IC1") (pin "7") (pinfunction "OSC_E_7") (pintype "bidirectional"))
    )
    (net (code "55") (name "unconnected-(IC4-BYPASS-Pad7)") (class "Default")
      (node (ref "IC4") (pin "7") (pinfunction "BYPASS_7") (pintype "passive"))
    )
    (net (code "56") (name "unconnected-(U$3-P$2-PadP$3)") (class "Default")
      (node (ref "U$3") (pin "P$3") (pinfunction "P$2_P$3") (pintype "bidirectional"))
    )
    (net (code "57") (name "unconnected-(U$10-P$2-PadP$3)") (class "Default")
      (node (ref "U$10") (pin "P$3") (pinfunction "P$2_P$3") (pintype "bidirectional"))
    )
    (net (code "58") (name "unconnected-(U$10-P$3-PadP$4)") (class "Default")
      (node (ref "U$10") (pin "P$4") (pinfunction "P$3_P$4") (pintype "bidirectional"))
    )
    (net (code "59") (name "unconnected-(U$10-P$4-PadP$5)") (class "Default")
      (node (ref "U$10") (pin "P$5") (pinfunction "P$4_P$5") (pintype "bidirectional"))
    )
    (net (code "60") (name "unconnected-(VR1-NC_1-Pad4)") (class "Default")
      (node (ref "VR1") (pin "4") (pinfunction "NC_1_4") (pintype "bidirectional"))
    )
    (net (code "61") (name "unconnected-(VR1-NC_2-Pad5)") (class "Default")
      (node (ref "VR1") (pin "5") (pinfunction "NC_2_5") (pintype "bidirectional"))
    )
    (net (code "62") (name "unconnected-(VR1-PadMH1)") (class "Default")
      (node (ref "VR1") (pin "MH1") (pinfunction "MH1_MH1") (pintype "bidirectional"))
    )
    (net (code "63") (name "unconnected-(VR1-PadMH2)") (class "Default")
      (node (ref "VR1") (pin "MH2") (pinfunction "MH2_MH2") (pintype "bidirectional"))
    )
  )
)
